# ADC.net
KiCad netlist of a schematic drawn in Altium Designer
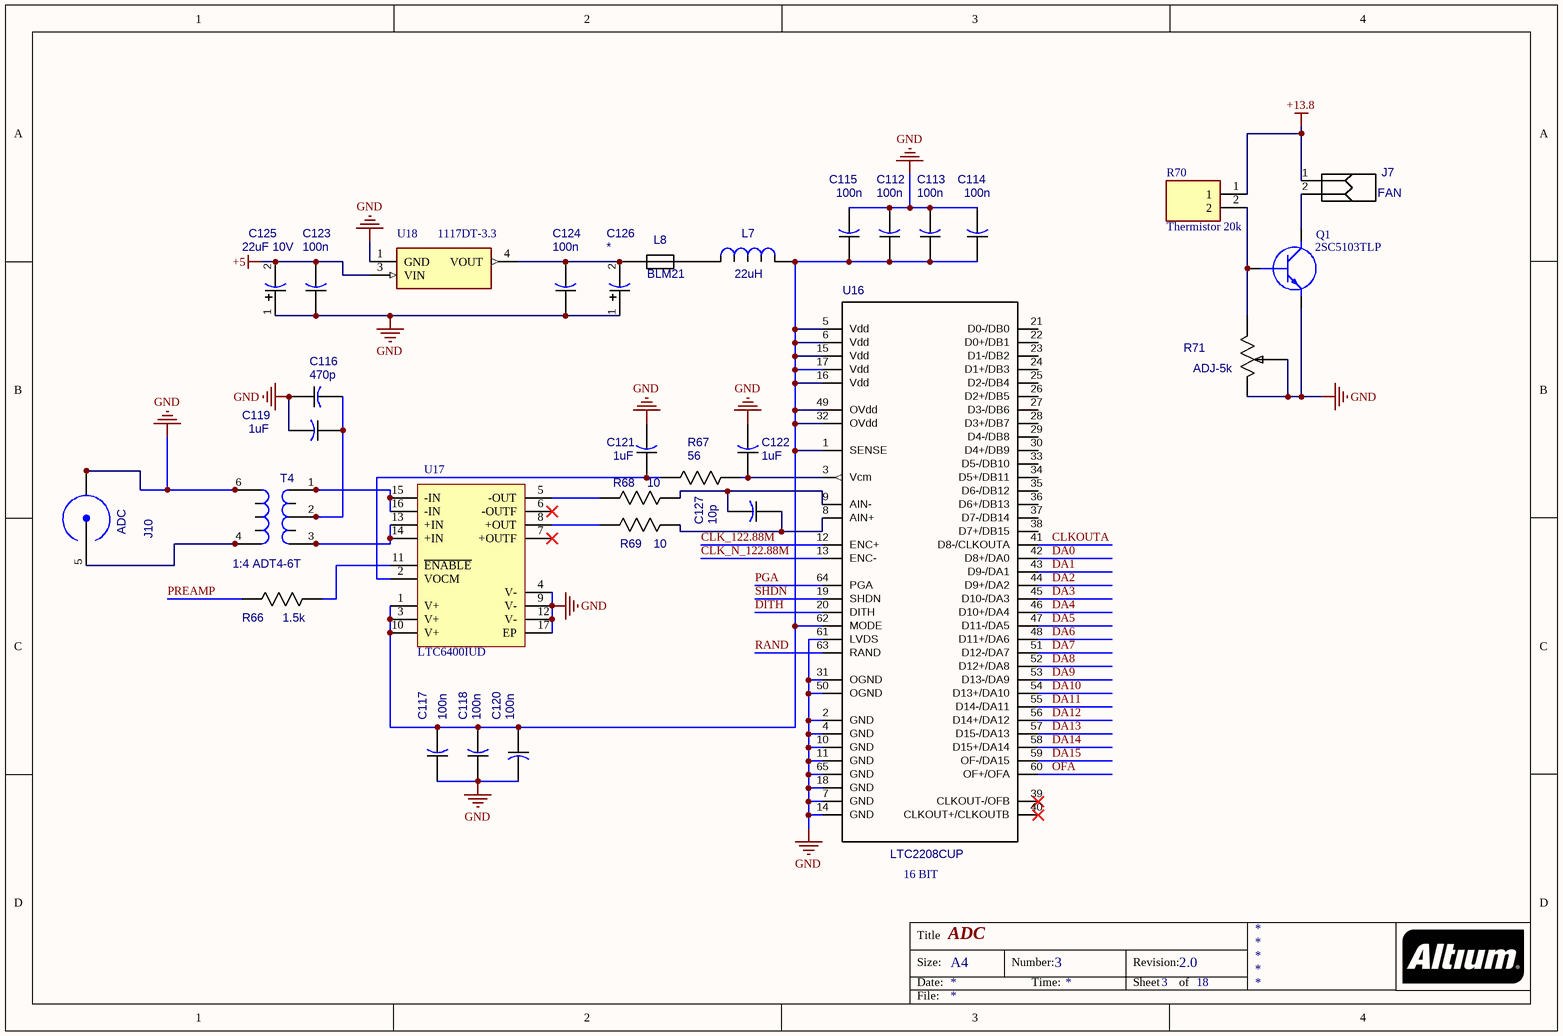
[diagram p0: ADC.SchDoc]

(export (version "E")
  (design (tool "Eeschema 10.0.6"))
  (components
    (comp (ref "C112")
      (value "100n")
      (footprint "CAP_0805")
      (description "CAP_0805")
      (libsource (lib "*") (part "CAP_0805"))
    )
    (comp (ref "C113")
      (value "100n")
      (footprint "CAP_0805")
      (description "CAP_0805")
      (libsource (lib "*") (part "CAP_0805"))
    )
    (comp (ref "C114")
      (value "100n")
      (footprint "CAP_0805")
      (description "CAP_0805")
      (libsource (lib "*") (part "CAP_0805"))
    )
    (comp (ref "C115")
      (value "100n")
      (footprint "CAP_0805")
      (description "CAP_0805")
      (libsource (lib "*") (part "CAP_0805"))
    )
    (comp (ref "C116")
      (value "470p")
      (footprint "CAP_0805")
      (description "CAP_0805")
      (libsource (lib "*") (part "CAP_0805"))
    )
    (comp (ref "C117")
      (value "100n")
      (footprint "CAP_0805")
      (description "CAP_0805")
      (libsource (lib "*") (part "CAP_0805"))
    )
    (comp (ref "C118")
      (value "100n")
      (footprint "CAP_0805")
      (description "CAP_0805")
      (libsource (lib "*") (part "CAP_0805"))
    )
    (comp (ref "C119")
      (value "1uF")
      (footprint "CAP_0805")
      (description "CAP_0805")
      (libsource (lib "*") (part "CAP_0805"))
    )
    (comp (ref "C120")
      (value "100n")
      (footprint "CAP_0805")
      (description "CAP_0805")
      (libsource (lib "*") (part "CAP_0805"))
    )
    (comp (ref "C121")
      (value "1uF")
      (footprint "CAP_0805")
      (description "CAP_0805")
      (libsource (lib "*") (part "CAP_0805"))
    )
    (comp (ref "C122")
      (value "1uF")
      (footprint "CAP_0805")
      (description "CAP_0805")
      (libsource (lib "*") (part "CAP_0805"))
    )
    (comp (ref "C123")
      (value "100n")
      (footprint "CAP_0805")
      (description "CAP_0805")
      (libsource (lib "*") (part "CAP_0805"))
    )
    (comp (ref "C124")
      (value "100n")
      (footprint "CAP_0805")
      (description "CAP_0805")
      (libsource (lib "*") (part "CAP_0805"))
    )
    (comp (ref "C125")
      (value "22uF 10V")
      (footprint "CAPAE_4.3x4.3h5.4")
      (description "CAPAE_4.3x4.3h5.4")
      (libsource (lib "MOTHERBOARD") (part "CAPAE_4.3x4.3h5.4"))
    )
    (comp (ref "C126")
      (value "22uF 10V")
      (footprint "CAPAE_4.3x4.3h5.4")
      (description "CAPAE_4.3x4.3h5.4")
      (fields (field (name "ALTIUM_VALUE") "*"))
      (libsource (lib "MOTHERBOARD") (part "CAPAE_4.3x4.3h5.4"))
    )
    (comp (ref "C127")
      (value "10p")
      (footprint "CAP_0805")
      (description "CAP_0805")
      (libsource (lib "*") (part "CAP_0805"))
    )
    (comp (ref "J7")
      (value "FAN")
      (footprint "51022-0200")
      (description "51022-0200")
      (libsource (lib "*") (part "51022-0200"))
    )
    (comp (ref "J10")
      (value "ADC")
      (footprint "31-5431")
      (description "SMA")
      (libsource (lib "RF-UNIT_1") (part "31-5431"))
    )
    (comp (ref "L7")
      (value "22uH")
      (footprint "IND_7x7")
      (description "IND_1206")
      (libsource (lib "*") (part "IND_1206"))
    )
    (comp (ref "L8")
      (value "BLM21")
      (footprint "CAP_0805")
      (libsource (lib "MOTHERBOARD_1") (part "IND_FERRITE_BEAD"))
    )
    (comp (ref "Q1")
      (value "2SC5103TLP")
      (footprint "SamacSys:2SC5103TLQ")
      (description "Transistor BJT NPN")
      (fields (field (name "MOUSER PART NUMBER") "755-2SC5103TLP"))
      (libsource (lib "*") (part "2SC5103TLP"))
    )
    (comp (ref "R66")
      (value "1.5k")
      (footprint "RES_0805")
      (description "RES_0805")
      (libsource (lib "") (part "RES_0805_1"))
    )
    (comp (ref "R67")
      (value "56")
      (footprint "RES_0805")
      (description "RES_0805")
      (libsource (lib "*") (part "RES_0805"))
    )
    (comp (ref "R68")
      (value "10")
      (footprint "RES_0603")
      (description "RES_0603")
      (libsource (lib "*") (part "RES_0603"))
    )
    (comp (ref "R69")
      (value "10")
      (footprint "RES_0603")
      (description "RES_0603")
      (libsource (lib "*") (part "RES_0603"))
    )
    (comp (ref "R70")
      (value "Thermistor 20k")
      (footprint "MF52A103F3950A1")
      (description "Thermistor")
      (fields (field (name "MANUFACTURER_PART_NUMBER") "MF52A103F3950(A1)"))
      (libsource (lib "*") (part "MF52A103F3950_A1_"))
    )
    (comp (ref "R71")
      (value "ADJ-5k")
      (footprint "306J")
      (description "306J")
      (libsource (lib "*") (part "306J"))
    )
    (comp (ref "T4")
      (value "1:4 ADT4-6T")
      (footprint "TRANSF_ACORE2")
      (description "Transformer")
      (libsource (lib "MOTHERBOARD_1") (part "TRANSF_ACORE2"))
    )
    (comp (ref "U16") (value "LTC2208CUP") (footprint "LTC2208CUP") (libsource (lib "*") (part "LTC2208CUP")))
    (comp (ref "U17")
      (value "LTC6400IUD")
      (footprint "LT-UD-16_N")
      (fields
        (field (name "MANUFACTURER") "Linear Technology")
        (field (name "LINEAR TECHNOLOGY PART NUMBER") "LTC6400-20")
        (field (name "PARTNUMBER") "LTC6400IUD-20#PBF")
      )
      (libsource (lib "Altium Content Vault") (part "LT-LTC640X-X-16"))
    )
    (comp (ref "U18")
      (value "1117DT-3.3")
      (footprint "SamacSys:TO228P991X238-3N")
      (description "LD1117DT33 DPAK")
      (fields
        (field (name "MANUFACTURER_PART_NUMBER") "LM1117DT-ADJ")
        (field (name "MOUSER PART NUMBER") "926-LM1117DT-ADJ")
      )
      (libsource (lib "*") (part "LM1117DT-ADJ"))
    )
  )
  (nets
    (net (code "1") (name "+5") (class "Default")
      (node (ref "C123") (pin "2") (pinfunction "2_2") (pintype "passive"))
      (node (ref "C125") (pin "2") (pinfunction "MINUS_2") (pintype "passive"))
      (node (ref "U18") (pin "3") (pinfunction "VIN_3") (pintype "input"))
    )
    (net (code "2") (name "+13.8") (class "Default")
      (node (ref "J7") (pin "1") (pinfunction "1_1") (pintype "passive"))
      (node (ref "R70") (pin "1") (pinfunction "1_1") (pintype "passive"))
    )
    (net (code "3") (name "/CLKOUTA") (class "Default")
      (node (ref "U16") (pin "41") (pinfunction "D8-/CLKOUTA_41") (pintype "passive"))
    )
    (net (code "4") (name "/CLK_122.88M") (class "Default")
      (node (ref "U16") (pin "12") (pinfunction "ENC+_12") (pintype "passive"))
    )
    (net (code "5") (name "/CLK_N_122.88M") (class "Default")
      (node (ref "U16") (pin "13") (pinfunction "ENC-_13") (pintype "passive"))
    )
    (net (code "6") (name "/DA0") (class "Default")
      (node (ref "U16") (pin "42") (pinfunction "D8+/DA0_42") (pintype "passive"))
    )
    (net (code "7") (name "/DA1") (class "Default")
      (node (ref "U16") (pin "43") (pinfunction "D9-/DA1_43") (pintype "passive"))
    )
    (net (code "8") (name "/DA2") (class "Default")
      (node (ref "U16") (pin "44") (pinfunction "D9+/DA2_44") (pintype "passive"))
    )
    (net (code "9") (name "/DA3") (class "Default")
      (node (ref "U16") (pin "45") (pinfunction "D10-/DA3_45") (pintype "passive"))
    )
    (net (code "10") (name "/DA4") (class "Default")
      (node (ref "U16") (pin "46") (pinfunction "D10+/DA4_46") (pintype "passive"))
    )
    (net (code "11") (name "/DA5") (class "Default")
      (node (ref "U16") (pin "47") (pinfunction "D11-/DA5_47") (pintype "passive"))
    )
    (net (code "12") (name "/DA6") (class "Default")
      (node (ref "U16") (pin "48") (pinfunction "D11+/DA6_48") (pintype "passive"))
    )
    (net (code "13") (name "/DA7") (class "Default")
      (node (ref "U16") (pin "51") (pinfunction "D12-/DA7_51") (pintype "passive"))
    )
    (net (code "14") (name "/DA8") (class "Default")
      (node (ref "U16") (pin "52") (pinfunction "D12+/DA8_52") (pintype "passive"))
    )
    (net (code "15") (name "/DA9") (class "Default")
      (node (ref "U16") (pin "53") (pinfunction "D13-/DA9_53") (pintype "passive"))
    )
    (net (code "16") (name "/DA10") (class "Default")
      (node (ref "U16") (pin "54") (pinfunction "D13+/DA10_54") (pintype "passive"))
    )
    (net (code "17") (name "/DA11") (class "Default")
      (node (ref "U16") (pin "55") (pinfunction "D14-/DA11_55") (pintype "passive"))
    )
    (net (code "18") (name "/DA12") (class "Default")
      (node (ref "U16") (pin "56") (pinfunction "D14+/DA12_56") (pintype "passive"))
    )
    (net (code "19") (name "/DA13") (class "Default")
      (node (ref "U16") (pin "57") (pinfunction "D15-/DA13_57") (pintype "passive"))
    )
    (net (code "20") (name "/DA14") (class "Default")
      (node (ref "U16") (pin "58") (pinfunction "D15+/DA14_58") (pintype "passive"))
    )
    (net (code "21") (name "/DA15") (class "Default")
      (node (ref "U16") (pin "59") (pinfunction "OF-/DA15_59") (pintype "passive"))
    )
    (net (code "22") (name "/DITH") (class "Default")
      (node (ref "U16") (pin "20") (pinfunction "DITH_20") (pintype "passive"))
    )
    (net (code "23") (name "/OFA") (class "Default")
      (node (ref "U16") (pin "60") (pinfunction "OF+/OFA_60") (pintype "passive"))
    )
    (net (code "24") (name "/PGA") (class "Default")
      (node (ref "U16") (pin "64") (pinfunction "PGA_64") (pintype "passive"))
    )
    (net (code "25") (name "/PREAMP") (class "Default")
      (node (ref "R66") (pin "2") (pinfunction "1_2") (pintype "passive"))
    )
    (net (code "26") (name "/RAND") (class "Default")
      (node (ref "U16") (pin "63") (pinfunction "RAND_63") (pintype "passive"))
    )
    (net (code "27") (name "/SHDN") (class "Default")
      (node (ref "U16") (pin "19") (pinfunction "SHDN_19") (pintype "passive"))
    )
    (net (code "28") (name "GND") (class "Default")
      (node (ref "C112") (pin "2") (pinfunction "2_2") (pintype "passive"))
      (node (ref "C113") (pin "2") (pinfunction "2_2") (pintype "passive"))
      (node (ref "C114") (pin "2") (pinfunction "2_2") (pintype "passive"))
      (node (ref "C115") (pin "2") (pinfunction "2_2") (pintype "passive"))
      (node (ref "C116") (pin "1") (pinfunction "1_1") (pintype "passive"))
      (node (ref "C117") (pin "1") (pinfunction "1_1") (pintype "passive"))
      (node (ref "C118") (pin "1") (pinfunction "1_1") (pintype "passive"))
      (node (ref "C119") (pin "2") (pinfunction "2_2") (pintype "passive"))
      (node (ref "C120") (pin "2") (pinfunction "2_2") (pintype "passive"))
      (node (ref "C121") (pin "2") (pinfunction "2_2") (pintype "passive"))
      (node (ref "C122") (pin "2") (pinfunction "2_2") (pintype "passive"))
      (node (ref "C123") (pin "1") (pinfunction "1_1") (pintype "passive"))
      (node (ref "C124") (pin "1") (pinfunction "1_1") (pintype "passive"))
      (node (ref "C125") (pin "1") (pinfunction "PLUS_1") (pintype "passive"))
      (node (ref "C126") (pin "1") (pinfunction "PLUS_1") (pintype "passive"))
      (node (ref "J10") (pin "1") (pinfunction "GND_1") (pintype "passive"))
      (node (ref "J10") (pin "2") (pinfunction "GND_2") (pintype "passive"))
      (node (ref "J10") (pin "3") (pinfunction "GND_3") (pintype "passive"))
      (node (ref "J10") (pin "4") (pinfunction "GND_4") (pintype "passive"))
      (node (ref "Q1") (pin "3") (pinfunction "E_3") (pintype "passive"))
      (node (ref "R71") (pin "1") (pinfunction "CCW_1") (pintype "passive"))
      (node (ref "R71") (pin "2") (pinfunction "W_2") (pintype "passive"))
      (node (ref "T4") (pin "10") (pinfunction "0_10") (pintype "passive"))
      (node (ref "T4") (pin "6") (pinfunction "P2_6") (pintype "passive"))
      (node (ref "U16") (pin "10") (pinfunction "GND_10") (pintype "passive"))
      (node (ref "U16") (pin "11") (pinfunction "GND_11") (pintype "passive"))
      (node (ref "U16") (pin "14") (pinfunction "GND_14") (pintype "passive"))
      (node (ref "U16") (pin "18") (pinfunction "GND_18") (pintype "passive"))
      (node (ref "U16") (pin "2") (pinfunction "GND_2") (pintype "passive"))
      (node (ref "U16") (pin "31") (pinfunction "OGND_31") (pintype "passive"))
      (node (ref "U16") (pin "4") (pinfunction "GND_4") (pintype "passive"))
      (node (ref "U16") (pin "50") (pinfunction "OGND_50") (pintype "passive"))
      (node (ref "U16") (pin "61") (pinfunction "LVDS_61") (pintype "passive"))
      (node (ref "U16") (pin "65") (pinfunction "GND_65") (pintype "passive"))
      (node (ref "U16") (pin "7") (pinfunction "GND_7") (pintype "passive"))
      (node (ref "U17") (pin "12") (pinfunction "V-_12") (pintype "power_in"))
      (node (ref "U17") (pin "17") (pinfunction "EP_17") (pintype "power_in"))
      (node (ref "U17") (pin "4") (pinfunction "V-_4") (pintype "power_in"))
      (node (ref "U17") (pin "9") (pinfunction "V-_9") (pintype "power_in"))
      (node (ref "U18") (pin "1") (pinfunction "GND_1") (pintype "passive"))
    )
    (net (code "29") (name "Net-(C126-MINUS)") (class "Default")
      (node (ref "C124") (pin "2") (pinfunction "2_2") (pintype "passive"))
      (node (ref "C126") (pin "2") (pinfunction "MINUS_2") (pintype "passive"))
      (node (ref "L8") (pin "1") (pinfunction "1_1") (pintype "passive"))
      (node (ref "U18") (pin "4") (pinfunction "VOUT_4") (pintype "output"))
    )
    (net (code "30") (name "Net-(J10-CON)") (class "Default")
      (node (ref "J10") (pin "5") (pinfunction "CON_5") (pintype "passive"))
      (node (ref "T4") (pin "11") (pinfunction "0_11") (pintype "passive"))
      (node (ref "T4") (pin "4") (pinfunction "P1_4") (pintype "passive"))
    )
    (net (code "31") (name "Net-(L7-Pad1)") (class "Default")
      (node (ref "L7") (pin "1") (pinfunction "1_1") (pintype "passive"))
      (node (ref "L8") (pin "2") (pinfunction "2_2") (pintype "passive"))
    )
    (net (code "32") (name "Net-(Q1-B)") (class "Default")
      (node (ref "Q1") (pin "1") (pinfunction "B_1") (pintype "passive"))
      (node (ref "R70") (pin "2") (pinfunction "2_2") (pintype "passive"))
      (node (ref "R71") (pin "3") (pinfunction "CW_3") (pintype "passive"))
    )
    (net (code "33") (name "Net-(Q1-C)") (class "Default")
      (node (ref "J7") (pin "2") (pinfunction "2_2") (pintype "passive"))
      (node (ref "Q1") (pin "2") (pinfunction "C_2") (pintype "passive"))
    )
    (net (code "34") (name "Net-(R66-2)") (class "Default")
      (node (ref "R66") (pin "1") (pinfunction "2_1") (pintype "passive"))
      (node (ref "U17") (pin "11") (pinfunction "~{ENABLE}_11") (pintype "passive"))
    )
    (net (code "35") (name "Net-(T4-S1)") (class "Default")
      (node (ref "T4") (pin "3") (pinfunction "S1_3") (pintype "passive"))
      (node (ref "T4") (pin "9") (pinfunction "0_9") (pintype "passive"))
      (node (ref "U17") (pin "13") (pinfunction "+IN_13") (pintype "passive"))
      (node (ref "U17") (pin "14") (pinfunction "+IN_14") (pintype "passive"))
    )
    (net (code "36") (name "Net-(T4-S2)") (class "Default")
      (node (ref "C116") (pin "2") (pinfunction "2_2") (pintype "passive"))
      (node (ref "C119") (pin "1") (pinfunction "1_1") (pintype "passive"))
      (node (ref "T4") (pin "2") (pinfunction "S2_2") (pintype "passive"))
      (node (ref "T4") (pin "8") (pinfunction "0_8") (pintype "passive"))
    )
    (net (code "37") (name "Net-(T4-S3)") (class "Default")
      (node (ref "T4") (pin "1") (pinfunction "S3_1") (pintype "passive"))
      (node (ref "T4") (pin "7") (pinfunction "0_7") (pintype "passive"))
      (node (ref "U17") (pin "15") (pinfunction "-IN_15") (pintype "passive"))
      (node (ref "U17") (pin "16") (pinfunction "-IN_16") (pintype "passive"))
    )
    (net (code "38") (name "Net-(U16-AIN+)") (class "Default")
      (node (ref "C127") (pin "1") (pinfunction "1_1") (pintype "passive"))
      (node (ref "R69") (pin "2") (pinfunction "2_2") (pintype "passive"))
      (node (ref "U16") (pin "8") (pinfunction "AIN+_8") (pintype "passive"))
    )
    (net (code "39") (name "Net-(U16-AIN-)") (class "Default")
      (node (ref "C127") (pin "2") (pinfunction "2_2") (pintype "passive"))
      (node (ref "R68") (pin "2") (pinfunction "2_2") (pintype "passive"))
      (node (ref "U16") (pin "9") (pinfunction "AIN-_9") (pintype "passive"))
    )
    (net (code "40") (name "Net-(U16-MODE)") (class "Default")
      (node (ref "C112") (pin "1") (pinfunction "1_1") (pintype "passive"))
      (node (ref "C113") (pin "1") (pinfunction "1_1") (pintype "passive"))
      (node (ref "C114") (pin "1") (pinfunction "1_1") (pintype "passive"))
      (node (ref "C115") (pin "1") (pinfunction "1_1") (pintype "passive"))
      (node (ref "C117") (pin "2") (pinfunction "2_2") (pintype "passive"))
      (node (ref "C118") (pin "2") (pinfunction "2_2") (pintype "passive"))
      (node (ref "C120") (pin "1") (pinfunction "1_1") (pintype "passive"))
      (node (ref "L7") (pin "2") (pinfunction "2_2") (pintype "passive"))
      (node (ref "U16") (pin "1") (pinfunction "SENSE_1") (pintype "passive"))
      (node (ref "U16") (pin "15") (pinfunction "Vdd_15") (pintype "passive"))
      (node (ref "U16") (pin "16") (pinfunction "Vdd_16") (pintype "passive"))
      (node (ref "U16") (pin "17") (pinfunction "Vdd_17") (pintype "passive"))
      (node (ref "U16") (pin "32") (pinfunction "OVdd_32") (pintype "passive"))
      (node (ref "U16") (pin "49") (pinfunction "OVdd_49") (pintype "passive"))
      (node (ref "U16") (pin "5") (pinfunction "Vdd_5") (pintype "passive"))
      (node (ref "U16") (pin "6") (pinfunction "Vdd_6") (pintype "passive"))
      (node (ref "U16") (pin "62") (pinfunction "MODE_62") (pintype "passive"))
      (node (ref "U17") (pin "1") (pinfunction "V+_1") (pintype "power_in"))
      (node (ref "U17") (pin "10") (pinfunction "V+_10") (pintype "power_in"))
      (node (ref "U17") (pin "3") (pinfunction "V+_3") (pintype "power_in"))
    )
    (net (code "41") (name "Net-(U16-Vcm)") (class "Default")
      (node (ref "C122") (pin "1") (pinfunction "1_1") (pintype "passive"))
      (node (ref "R67") (pin "2") (pinfunction "2_2") (pintype "passive"))
      (node (ref "U16") (pin "3") (pinfunction "Vcm_3") (pintype "output"))
    )
    (net (code "42") (name "Net-(U17-+OUT)") (class "Default")
      (node (ref "R69") (pin "1") (pinfunction "1_1") (pintype "passive"))
      (node (ref "U17") (pin "8") (pinfunction "+OUT_8") (pintype "passive"))
    )
    (net (code "43") (name "Net-(U17--OUT)") (class "Default")
      (node (ref "R68") (pin "1") (pinfunction "1_1") (pintype "passive"))
      (node (ref "U17") (pin "5") (pinfunction "-OUT_5") (pintype "passive"))
    )
    (net (code "44") (name "Net-(U17-VOCM)") (class "Default")
      (node (ref "C121") (pin "1") (pinfunction "1_1") (pintype "passive"))
      (node (ref "R67") (pin "1") (pinfunction "1_1") (pintype "passive"))
      (node (ref "U17") (pin "2") (pinfunction "VOCM_2") (pintype "passive"))
    )
    (net (code "45") (name "unconnected-(U16-CLKOUT+{slash}CLKOUTB-Pad40)") (class "Default")
      (node (ref "U16") (pin "40") (pinfunction "CLKOUT+/CLKOUTB_40") (pintype "passive+no_connect"))
    )
    (net (code "46") (name "unconnected-(U16-CLKOUT-{slash}OFB-Pad39)") (class "Default")
      (node (ref "U16") (pin "39") (pinfunction "CLKOUT-/OFB_39") (pintype "passive+no_connect"))
    )
    (net (code "47") (name "unconnected-(U16-D0+{slash}DB1-Pad22)") (class "Default")
      (node (ref "U16") (pin "22") (pinfunction "D0+/DB1_22") (pintype "passive"))
    )
    (net (code "48") (name "unconnected-(U16-D0-{slash}DB0-Pad21)") (class "Default")
      (node (ref "U16") (pin "21") (pinfunction "D0-/DB0_21") (pintype "passive"))
    )
    (net (code "49") (name "unconnected-(U16-D1+{slash}DB3-Pad24)") (class "Default")
      (node (ref "U16") (pin "24") (pinfunction "D1+/DB3_24") (pintype "passive"))
    )
    (net (code "50") (name "unconnected-(U16-D1-{slash}DB2-Pad23)") (class "Default")
      (node (ref "U16") (pin "23") (pinfunction "D1-/DB2_23") (pintype "passive"))
    )
    (net (code "51") (name "unconnected-(U16-D2+{slash}DB5-Pad26)") (class "Default")
      (node (ref "U16") (pin "26") (pinfunction "D2+/DB5_26") (pintype "passive"))
    )
    (net (code "52") (name "unconnected-(U16-D2-{slash}DB4-Pad25)") (class "Default")
      (node (ref "U16") (pin "25") (pinfunction "D2-/DB4_25") (pintype "passive"))
    )
    (net (code "53") (name "unconnected-(U16-D3+{slash}DB7-Pad28)") (class "Default")
      (node (ref "U16") (pin "28") (pinfunction "D3+/DB7_28") (pintype "passive"))
    )
    (net (code "54") (name "unconnected-(U16-D3-{slash}DB6-Pad27)") (class "Default")
      (node (ref "U16") (pin "27") (pinfunction "D3-/DB6_27") (pintype "passive"))
    )
    (net (code "55") (name "unconnected-(U16-D4+{slash}DB9-Pad30)") (class "Default")
      (node (ref "U16") (pin "30") (pinfunction "D4+/DB9_30") (pintype "passive"))
    )
    (net (code "56") (name "unconnected-(U16-D4-{slash}DB8-Pad29)") (class "Default")
      (node (ref "U16") (pin "29") (pinfunction "D4-/DB8_29") (pintype "passive"))
    )
    (net (code "57") (name "unconnected-(U16-D5+{slash}DB11-Pad34)") (class "Default")
      (node (ref "U16") (pin "34") (pinfunction "D5+/DB11_34") (pintype "passive"))
    )
    (net (code "58") (name "unconnected-(U16-D5-{slash}DB10-Pad33)") (class "Default")
      (node (ref "U16") (pin "33") (pinfunction "D5-/DB10_33") (pintype "passive"))
    )
    (net (code "59") (name "unconnected-(U16-D6+{slash}DB13-Pad36)") (class "Default")
      (node (ref "U16") (pin "36") (pinfunction "D6+/DB13_36") (pintype "passive"))
    )
    (net (code "60") (name "unconnected-(U16-D6-{slash}DB12-Pad35)") (class "Default")
      (node (ref "U16") (pin "35") (pinfunction "D6-/DB12_35") (pintype "passive"))
    )
    (net (code "61") (name "unconnected-(U16-D7+{slash}DB15-Pad38)") (class "Default")
      (node (ref "U16") (pin "38") (pinfunction "D7+/DB15_38") (pintype "passive"))
    )
    (net (code "62") (name "unconnected-(U16-D7-{slash}DB14-Pad37)") (class "Default")
      (node (ref "U16") (pin "37") (pinfunction "D7-/DB14_37") (pintype "passive"))
    )
    (net (code "63") (name "unconnected-(U17-+OUTF-Pad7)") (class "Default")
      (node (ref "U17") (pin "7") (pinfunction "+OUTF_7") (pintype "passive+no_connect"))
    )
    (net (code "64") (name "unconnected-(U17--OUTF-Pad6)") (class "Default")
      (node (ref "U17") (pin "6") (pinfunction "-OUTF_6") (pintype "passive+no_connect"))
    )
  )
)
